# DRV8843.net
KiCad netlist of a schematic drawn in Altium Designer
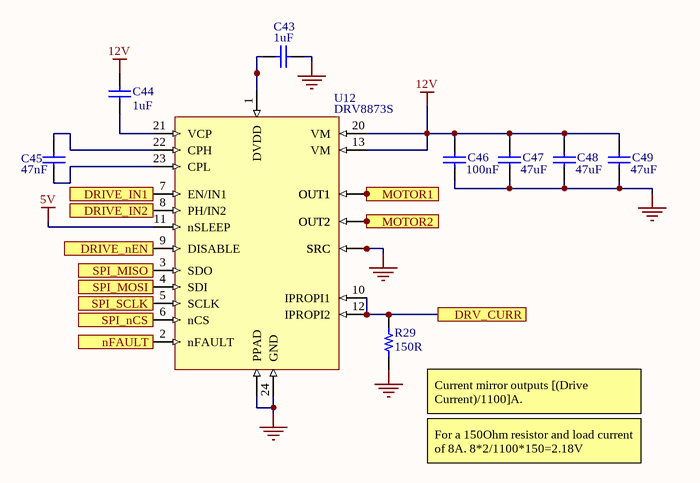
[diagram p0: DRV8843.SchDoc]

(export (version "E")
  (design (tool "Eeschema 10.0.6"))
  (components
    (comp (ref "C43")
      (value "1uF")
      (footprint "0402")
      (fields (field (name "Comment") "Cap") (field (name "PUBLISHER") "Altium Limited"))
      (libsource (lib "Parts") (part "Cap"))
    )
    (comp (ref "C44")
      (value "1uF")
      (footprint "0402")
      (fields (field (name "Comment") "Cap") (field (name "PUBLISHER") "Altium Limited"))
      (libsource (lib "Parts") (part "Cap"))
    )
    (comp (ref "C45")
      (value "47nF")
      (footprint "0402")
      (fields (field (name "Comment") "Cap") (field (name "PUBLISHER") "Altium Limited"))
      (libsource (lib "Parts") (part "Cap"))
    )
    (comp (ref "C46")
      (value "100nF")
      (footprint "0402")
      (fields (field (name "Comment") "Cap") (field (name "PUBLISHER") "Altium Limited"))
      (libsource (lib "Parts") (part "Cap"))
    )
    (comp (ref "C47")
      (value "47uF")
      (footprint "1206")
      (fields (field (name "Comment") "Cap") (field (name "PUBLISHER") "Altium Limited"))
      (libsource (lib "Parts") (part "Cap"))
    )
    (comp (ref "C48")
      (value "47uF")
      (footprint "1206")
      (fields (field (name "Comment") "Cap") (field (name "PUBLISHER") "Altium Limited"))
      (libsource (lib "Parts") (part "Cap"))
    )
    (comp (ref "C49")
      (value "47uF")
      (footprint "1206")
      (fields (field (name "Comment") "Cap") (field (name "PUBLISHER") "Altium Limited"))
      (libsource (lib "Parts") (part "Cap"))
    )
    (comp (ref "R29")
      (value "150R")
      (footprint "0805 - duplicate")
      (libsource (lib "Parts") (part "Resistor"))
    )
    (comp (ref "U12") (value "DRV8873S") (footprint "HTSSOP24") (libsource (lib "Parts") (part "DRV8873S")))
  )
  (nets
    (net (code "1") (name "/DRIVE_IN1") (class "Default")
      (node (ref "U12") (pin "7") (pinfunction "EN/IN1_7") (pintype "input"))
    )
    (net (code "2") (name "/DRIVE_IN2") (class "Default")
      (node (ref "U12") (pin "8") (pinfunction "PH/IN2_8") (pintype "input"))
    )
    (net (code "3") (name "/DRIVE_nEN") (class "Default")
      (node (ref "U12") (pin "9") (pinfunction "DISABLE_9") (pintype "input"))
    )
    (net (code "4") (name "/DRV_CURR") (class "Default")
      (node (ref "R29") (pin "2") (pinfunction "2_2") (pintype "passive"))
      (node (ref "U12") (pin "10") (pinfunction "IPROPI1_10") (pintype "input"))
      (node (ref "U12") (pin "12") (pinfunction "IPROPI2_12") (pintype "input"))
    )
    (net (code "5") (name "/MOTOR1") (class "Default")
      (node (ref "U12") (pin "18") (pinfunction "OUT1_18") (pintype "input"))
      (node (ref "U12") (pin "19") (pinfunction "OUT1_19") (pintype "input"))
    )
    (net (code "6") (name "/MOTOR2") (class "Default")
      (node (ref "U12") (pin "14") (pinfunction "OUT2_14") (pintype "input"))
      (node (ref "U12") (pin "15") (pinfunction "OUT2_15") (pintype "input"))
    )
    (net (code "7") (name "/SPI_MISO") (class "Default")
      (node (ref "U12") (pin "3") (pinfunction "SDO_3") (pintype "input"))
    )
    (net (code "8") (name "/SPI_MOSI") (class "Default")
      (node (ref "U12") (pin "4") (pinfunction "SDI_4") (pintype "input"))
    )
    (net (code "9") (name "/SPI_SCLK") (class "Default")
      (node (ref "U12") (pin "5") (pinfunction "SCLK_5") (pintype "input"))
    )
    (net (code "10") (name "/SPI_nCS") (class "Default")
      (node (ref "U12") (pin "6") (pinfunction "nCS_6") (pintype "input"))
    )
    (net (code "11") (name "/nFAULT") (class "Default")
      (node (ref "U12") (pin "2") (pinfunction "nFAULT_2") (pintype "input"))
    )
    (net (code "12") (name "5V") (class "Default")
      (node (ref "U12") (pin "11") (pinfunction "nSLEEP_11") (pintype "input"))
    )
    (net (code "13") (name "12V") (class "Default")
      (node (ref "C44") (pin "2") (pinfunction "2_2") (pintype "passive"))
      (node (ref "C46") (pin "2") (pinfunction "2_2") (pintype "passive"))
      (node (ref "C47") (pin "2") (pinfunction "2_2") (pintype "passive"))
      (node (ref "C48") (pin "2") (pinfunction "2_2") (pintype "passive"))
      (node (ref "C49") (pin "2") (pinfunction "2_2") (pintype "passive"))
      (node (ref "U12") (pin "13") (pinfunction "VM_13") (pintype "input"))
      (node (ref "U12") (pin "20") (pinfunction "VM_20") (pintype "input"))
    )
    (net (code "14") (name "GND") (class "Default")
      (node (ref "C43") (pin "2") (pinfunction "2_2") (pintype "passive"))
      (node (ref "C46") (pin "1") (pinfunction "1_1") (pintype "passive"))
      (node (ref "C47") (pin "1") (pinfunction "1_1") (pintype "passive"))
      (node (ref "C48") (pin "1") (pinfunction "1_1") (pintype "passive"))
      (node (ref "C49") (pin "1") (pinfunction "1_1") (pintype "passive"))
      (node (ref "R29") (pin "1") (pinfunction "1_1") (pintype "passive"))
      (node (ref "U12") (pin "16") (pinfunction "SRC_16") (pintype "input"))
      (node (ref "U12") (pin "17") (pinfunction "SRC_17") (pintype "input"))
      (node (ref "U12") (pin "24") (pinfunction "GND_24") (pintype "input"))
      (node (ref "U12") (pin "THERM") (pinfunction "PPAD_THERM") (pintype "input"))
    )
    (net (code "15") (name "Net-(U12-CPH)") (class "Default")
      (node (ref "C45") (pin "2") (pinfunction "2_2") (pintype "passive"))
      (node (ref "U12") (pin "22") (pinfunction "CPH_22") (pintype "input"))
    )
    (net (code "16") (name "Net-(U12-CPL)") (class "Default")
      (node (ref "C45") (pin "1") (pinfunction "1_1") (pintype "passive"))
      (node (ref "U12") (pin "23") (pinfunction "CPL_23") (pintype "input"))
    )
    (net (code "17") (name "Net-(U12-DVDD)") (class "Default")
      (node (ref "C43") (pin "1") (pinfunction "1_1") (pintype "passive"))
      (node (ref "U12") (pin "1") (pinfunction "DVDD_1") (pintype "input"))
    )
    (net (code "18") (name "Net-(U12-VCP)") (class "Default")
      (node (ref "C44") (pin "1") (pinfunction "1_1") (pintype "passive"))
      (node (ref "U12") (pin "21") (pinfunction "VCP_21") (pintype "input"))
    )
  )
)
